# mimic1568_DtoA.net
KiCad netlist of a schematic drawn in EAGLE
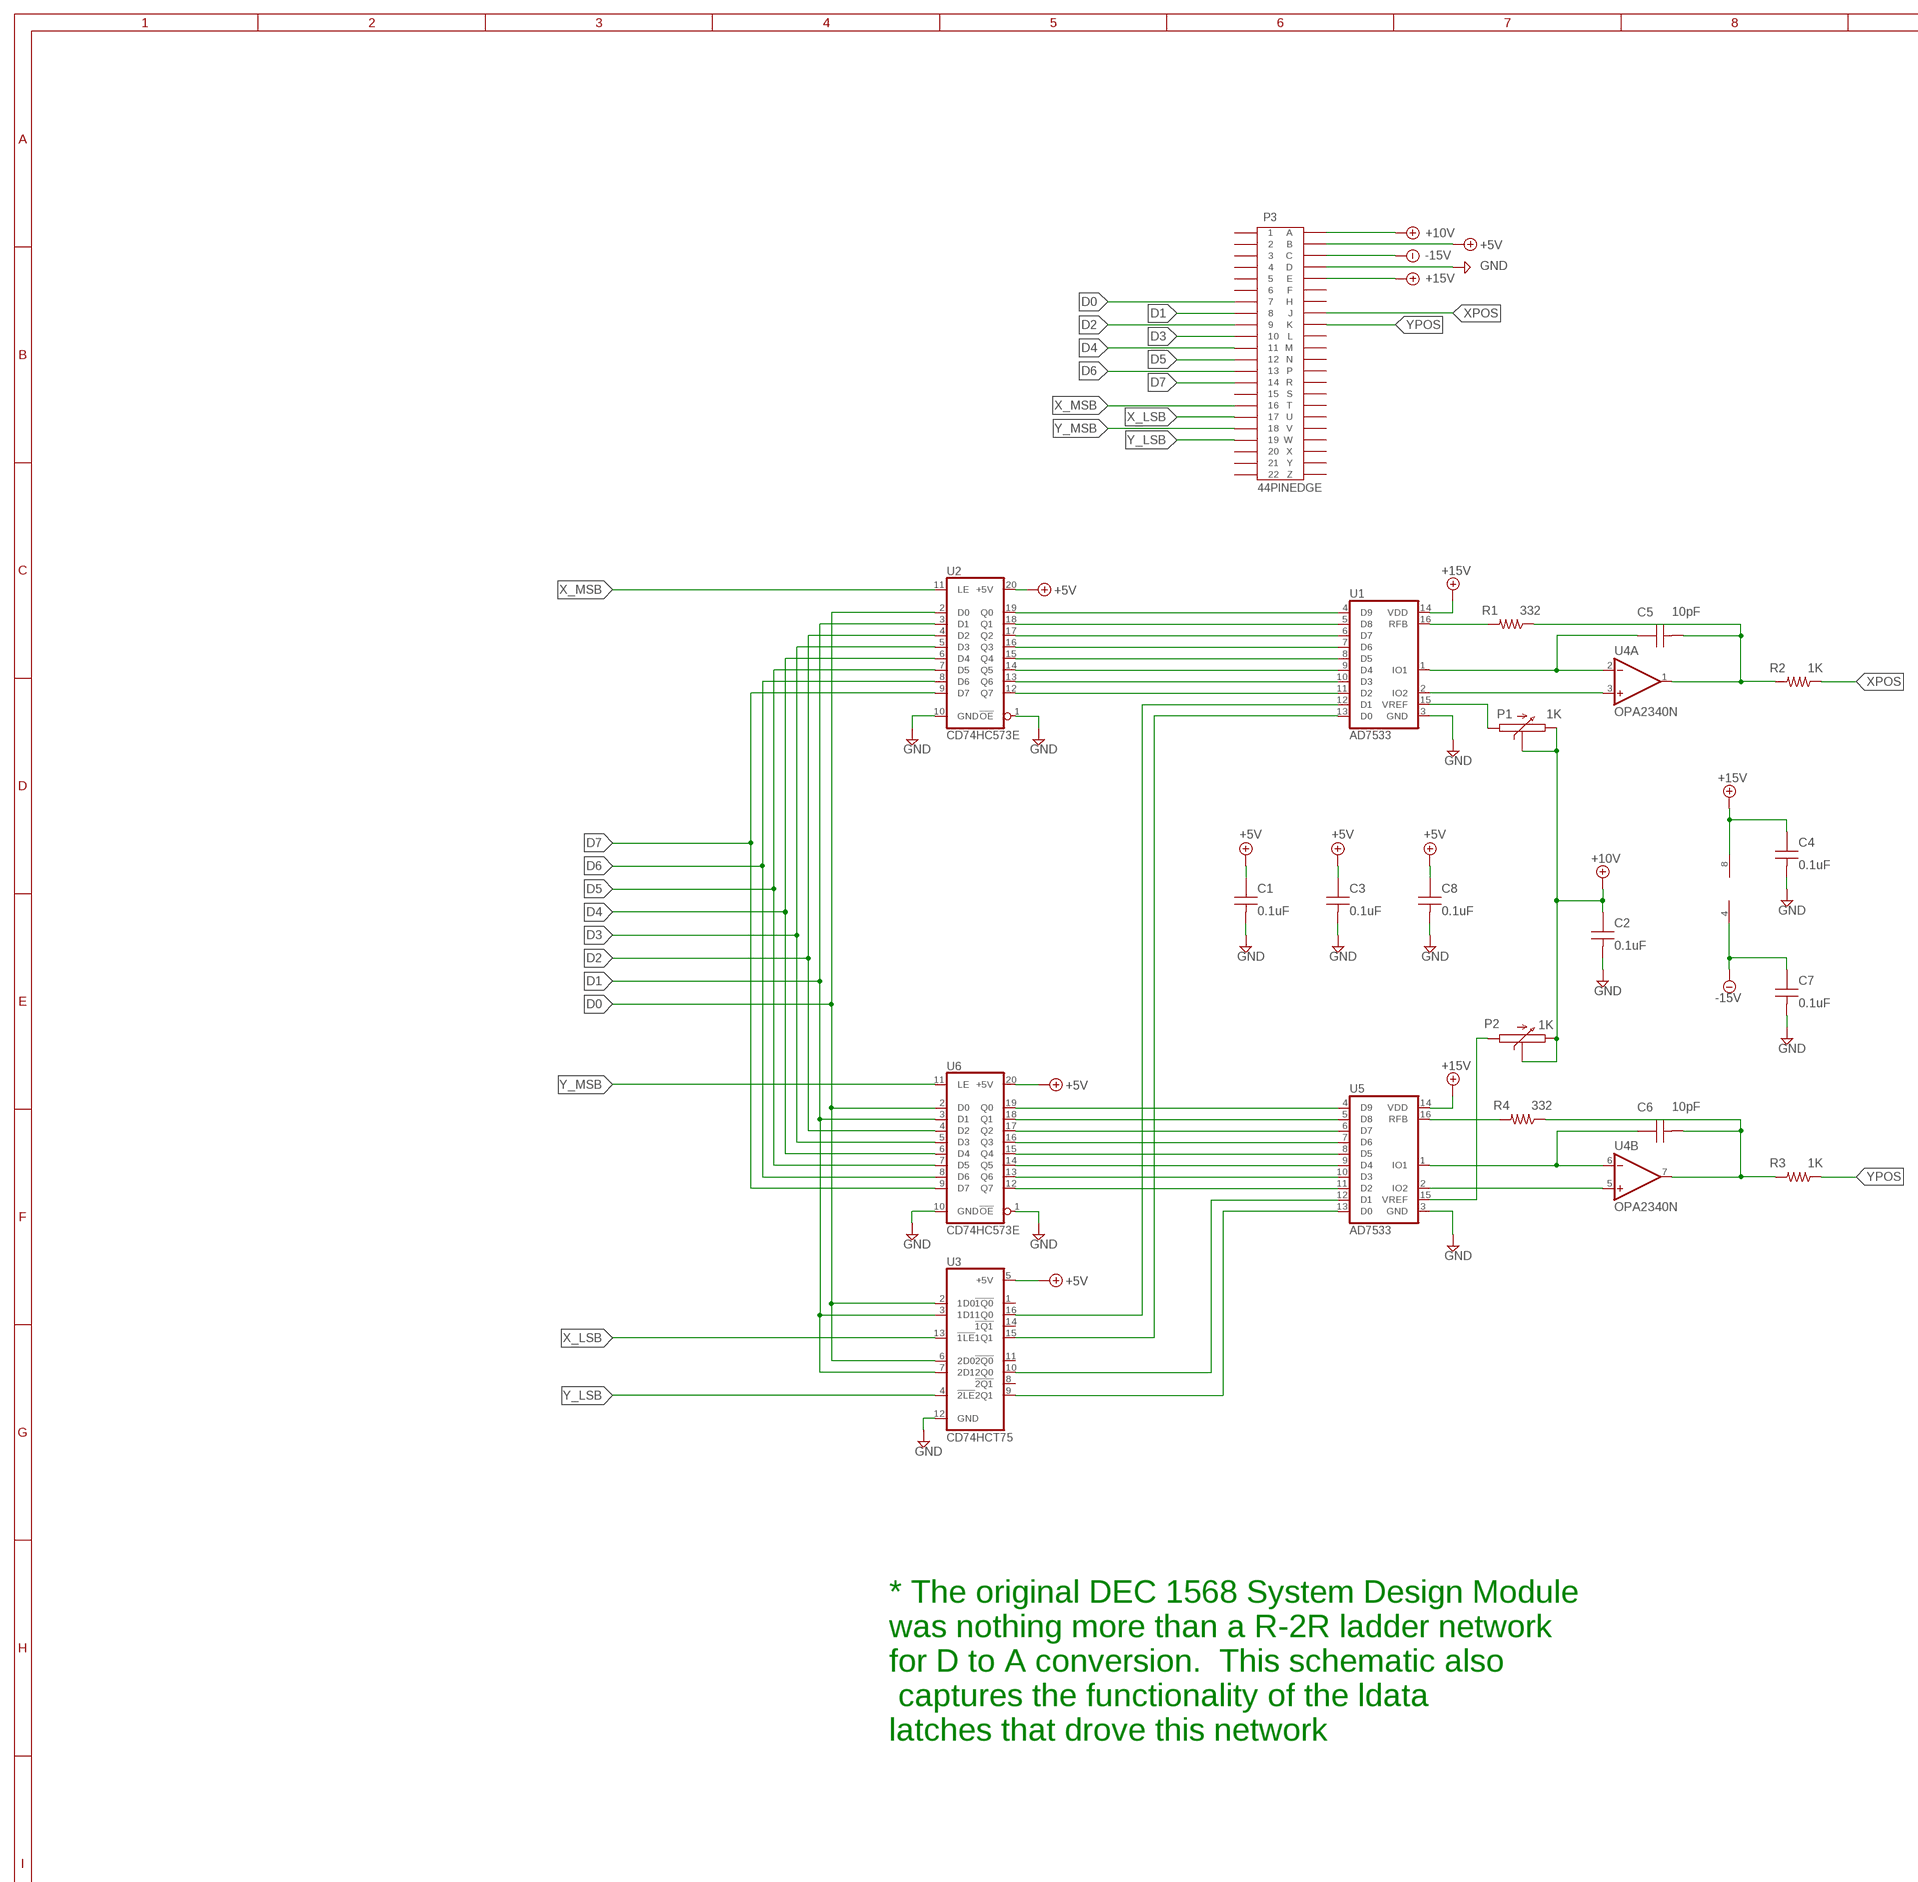
[diagram p0: schematic, sheet 1, part 1 of 2]
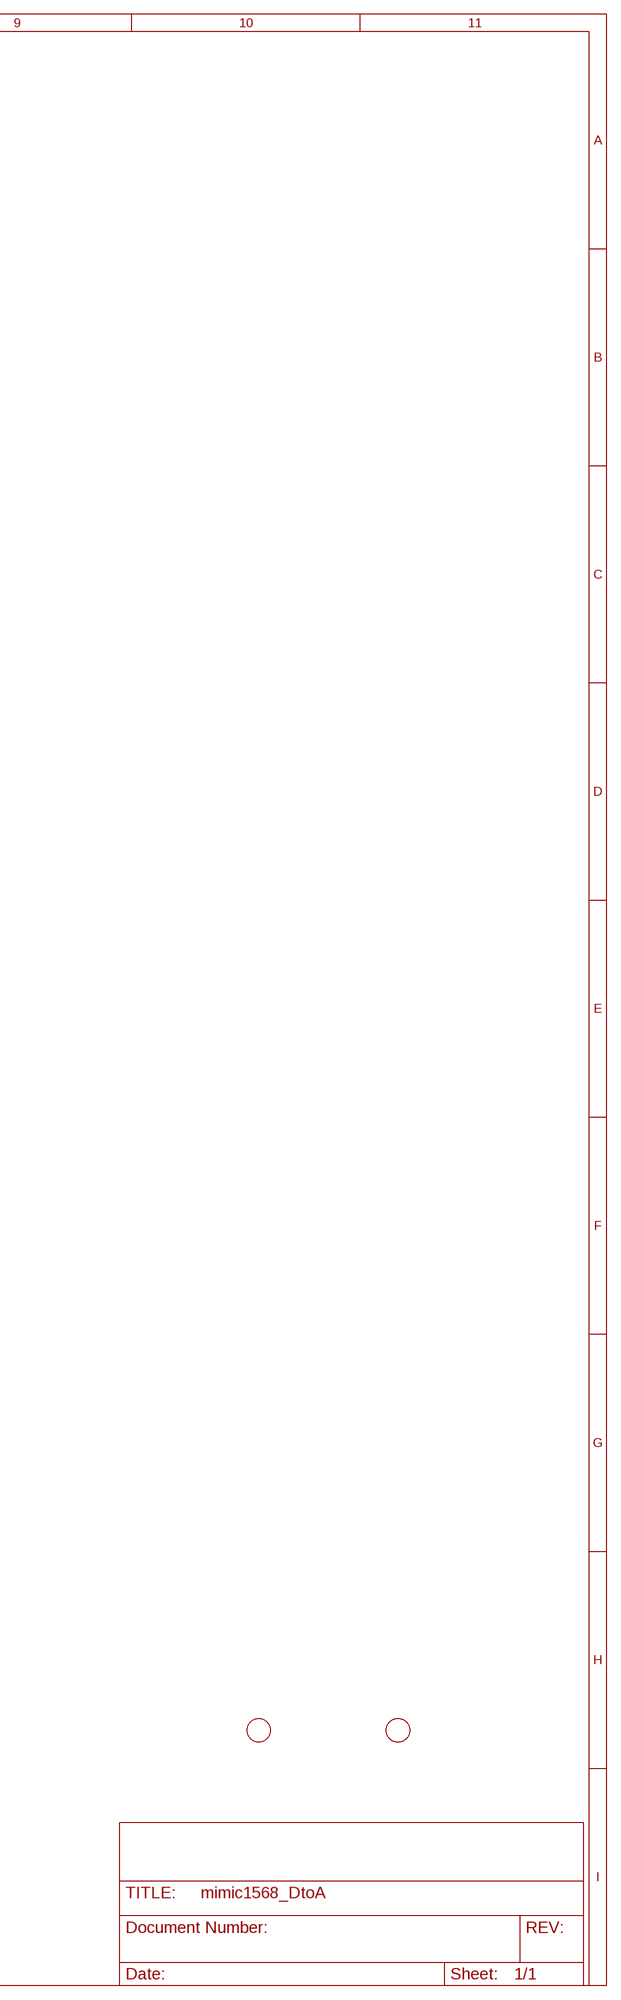
[diagram p1: schematic, sheet 1, part 2 of 2]

(export (version "E")
  (design (tool "Eeschema 10.0.6"))
  (components
    (comp (ref "C1")
      (value "0.1uF")
      (footprint "eagle-import:5MM_TH")
      (fields (field (name "MPN") "FA26X8R2A104KNU06"))
      (libsource (lib "eagle-import") (part "CAP0.1UF100V"))
    )
    (comp (ref "C2")
      (value "0.1uF")
      (footprint "eagle-import:5MM_TH")
      (fields (field (name "MPN") "FA26X8R2A104KNU06"))
      (libsource (lib "eagle-import") (part "CAP0.1UF100V"))
    )
    (comp (ref "C3")
      (value "0.1uF")
      (footprint "eagle-import:5MM_TH")
      (fields (field (name "MPN") "FA26X8R2A104KNU06"))
      (libsource (lib "eagle-import") (part "CAP0.1UF100V"))
    )
    (comp (ref "C4")
      (value "0.1uF")
      (footprint "eagle-import:5MM_TH")
      (fields (field (name "MPN") "FA26X8R2A104KNU06"))
      (libsource (lib "eagle-import") (part "CAP0.1UF100V"))
    )
    (comp (ref "C5")
      (value "10pF")
      (footprint "eagle-import:5MM_TH")
      (fields (field (name "MPN") "FA26X8R2A104KNU06"))
      (libsource (lib "eagle-import") (part "CAP0.1UF100V"))
    )
    (comp (ref "C6")
      (value "10pF")
      (footprint "eagle-import:5MM_TH")
      (fields (field (name "MPN") "FA26X8R2A104KNU06"))
      (libsource (lib "eagle-import") (part "CAP0.1UF100V"))
    )
    (comp (ref "C7")
      (value "0.1uF")
      (footprint "eagle-import:5MM_TH")
      (fields (field (name "MPN") "FA26X8R2A104KNU06"))
      (libsource (lib "eagle-import") (part "CAP0.1UF100V"))
    )
    (comp (ref "C8")
      (value "0.1uF")
      (footprint "eagle-import:5MM_TH")
      (fields (field (name "MPN") "FA26X8R2A104KNU06"))
      (libsource (lib "eagle-import") (part "CAP0.1UF100V"))
    )
    (comp (ref "P1")
      (value "1K")
      (footprint "eagle-import:3006P")
      (libsource (lib "eagle-import") (part "POT-3006P"))
    )
    (comp (ref "P2")
      (value "1K")
      (footprint "eagle-import:3006P")
      (libsource (lib "eagle-import") (part "POT-3006P"))
    )
    (comp (ref "P3")
      (value "44PINEDGE")
      (footprint "eagle-import:44PINEDGE")
      (libsource (lib "eagle-import") (part "44PINEDGE"))
    )
    (comp (ref "R1")
      (value "332")
      (footprint "eagle-import:0207_10")
      (libsource (lib "eagle-import") (part "R-1/4WATT"))
    )
    (comp (ref "R2")
      (value "1K")
      (footprint "eagle-import:0207_10")
      (libsource (lib "eagle-import") (part "R-1/4WATT"))
    )
    (comp (ref "R3")
      (value "1K")
      (footprint "eagle-import:0207_10")
      (libsource (lib "eagle-import") (part "R-1/4WATT"))
    )
    (comp (ref "R4")
      (value "332")
      (footprint "eagle-import:0207_10")
      (libsource (lib "eagle-import") (part "R-1/4WATT"))
    )
    (comp (ref "U$1")
      (value "FIDUCIAL")
      (footprint "eagle-import:FIDUCIAL_1MM")
      (libsource (lib "eagle-import") (part "FIDUCIAL"))
    )
    (comp (ref "U$2")
      (value "FIDUCIAL")
      (footprint "eagle-import:FIDUCIAL_1MM")
      (libsource (lib "eagle-import") (part "FIDUCIAL"))
    )
    (comp (ref "U1")
      (value "AD7533")
      (footprint "eagle-import:DIP-16")
      (libsource (lib "eagle-import") (part "AD7533"))
    )
    (comp (ref "U2")
      (value "CD74HC573E")
      (footprint "eagle-import:DIP-20")
      (libsource (lib "eagle-import") (part "CD74HC573E"))
    )
    (comp (ref "U3")
      (value "CD74HCT75")
      (footprint "eagle-import:DIP-16")
      (libsource (lib "eagle-import") (part "CD74HCT75"))
    )
    (comp (ref "U4")
      (value "OPA2340N")
      (footprint "eagle-import:DIP-08")
      (libsource (lib "eagle-import") (part "OPA2340N"))
    )
    (comp (ref "U5")
      (value "AD7533")
      (footprint "eagle-import:DIP-16")
      (libsource (lib "eagle-import") (part "AD7533"))
    )
    (comp (ref "U6")
      (value "CD74HC573E")
      (footprint "eagle-import:DIP-20")
      (libsource (lib "eagle-import") (part "CD74HC573E"))
    )
  )
  (nets
    (net (code "1") (name "+5V") (class "Default")
      (node (ref "C1") (pin "1") (pinfunction "1_1") (pintype "passive"))
      (node (ref "C3") (pin "1") (pinfunction "1_1") (pintype "passive"))
      (node (ref "C8") (pin "1") (pinfunction "1_1") (pintype "passive"))
      (node (ref "P3") (pin "B") (pinfunction "B_B") (pintype "passive"))
      (node (ref "U2") (pin "20") (pinfunction "+5V_20") (pintype "power_in"))
      (node (ref "U3") (pin "5") (pinfunction "+5V_5") (pintype "power_in"))
      (node (ref "U6") (pin "20") (pinfunction "+5V_20") (pintype "power_in"))
    )
    (net (code "2") (name "+10V") (class "Default")
      (node (ref "C2") (pin "1") (pinfunction "1_1") (pintype "passive"))
      (node (ref "P1") (pin "2") (pinfunction "2_2") (pintype "passive"))
      (node (ref "P1") (pin "3") (pinfunction "3_3") (pintype "passive"))
      (node (ref "P2") (pin "2") (pinfunction "2_2") (pintype "passive"))
      (node (ref "P2") (pin "3") (pinfunction "3_3") (pintype "passive"))
      (node (ref "P3") (pin "A") (pinfunction "A_A") (pintype "passive"))
    )
    (net (code "3") (name "+15V") (class "Default")
      (node (ref "C4") (pin "1") (pinfunction "1_1") (pintype "passive"))
      (node (ref "P3") (pin "E") (pinfunction "E_E") (pintype "passive"))
      (node (ref "U1") (pin "14") (pinfunction "VDD_14") (pintype "power_in"))
      (node (ref "U4") (pin "8") (pinfunction "V+_8") (pintype "power_in"))
      (node (ref "U5") (pin "14") (pinfunction "VDD_14") (pintype "power_in"))
    )
    (net (code "4") (name "-15V") (class "Default")
      (node (ref "C7") (pin "1") (pinfunction "1_1") (pintype "passive"))
      (node (ref "P3") (pin "C") (pinfunction "C_C") (pintype "passive"))
      (node (ref "U4") (pin "4") (pinfunction "V-_4") (pintype "power_in"))
    )
    (net (code "5") (name "D0") (class "Default")
      (node (ref "P3") (pin "7") (pinfunction "7_7") (pintype "passive"))
      (node (ref "U2") (pin "2") (pinfunction "D0_2") (pintype "input"))
      (node (ref "U3") (pin "2") (pinfunction "1D0_2") (pintype "input"))
      (node (ref "U3") (pin "6") (pinfunction "2D0_6") (pintype "input"))
      (node (ref "U6") (pin "2") (pinfunction "D0_2") (pintype "input"))
    )
    (net (code "6") (name "D1") (class "Default")
      (node (ref "P3") (pin "8") (pinfunction "8_8") (pintype "passive"))
      (node (ref "U2") (pin "3") (pinfunction "D1_3") (pintype "input"))
      (node (ref "U3") (pin "3") (pinfunction "1D1_3") (pintype "input"))
      (node (ref "U3") (pin "7") (pinfunction "2D1_7") (pintype "input"))
      (node (ref "U6") (pin "3") (pinfunction "D1_3") (pintype "input"))
    )
    (net (code "7") (name "D2") (class "Default")
      (node (ref "P3") (pin "9") (pinfunction "9_9") (pintype "passive"))
      (node (ref "U2") (pin "4") (pinfunction "D2_4") (pintype "input"))
      (node (ref "U6") (pin "4") (pinfunction "D2_4") (pintype "input"))
    )
    (net (code "8") (name "D3") (class "Default")
      (node (ref "P3") (pin "10") (pinfunction "10_10") (pintype "passive"))
      (node (ref "U2") (pin "5") (pinfunction "D3_5") (pintype "input"))
      (node (ref "U6") (pin "5") (pinfunction "D3_5") (pintype "input"))
    )
    (net (code "9") (name "D4") (class "Default")
      (node (ref "P3") (pin "11") (pinfunction "11_11") (pintype "passive"))
      (node (ref "U2") (pin "6") (pinfunction "D4_6") (pintype "input"))
      (node (ref "U6") (pin "6") (pinfunction "D4_6") (pintype "input"))
    )
    (net (code "10") (name "D5") (class "Default")
      (node (ref "P3") (pin "12") (pinfunction "12_12") (pintype "passive"))
      (node (ref "U2") (pin "7") (pinfunction "D5_7") (pintype "input"))
      (node (ref "U6") (pin "7") (pinfunction "D5_7") (pintype "input"))
    )
    (net (code "11") (name "D6") (class "Default")
      (node (ref "P3") (pin "13") (pinfunction "13_13") (pintype "passive"))
      (node (ref "U2") (pin "8") (pinfunction "D6_8") (pintype "input"))
      (node (ref "U6") (pin "8") (pinfunction "D6_8") (pintype "input"))
    )
    (net (code "12") (name "D7") (class "Default")
      (node (ref "P3") (pin "14") (pinfunction "14_14") (pintype "passive"))
      (node (ref "U2") (pin "9") (pinfunction "D7_9") (pintype "input"))
      (node (ref "U6") (pin "9") (pinfunction "D7_9") (pintype "input"))
    )
    (net (code "13") (name "GND") (class "Default")
      (node (ref "C1") (pin "2") (pinfunction "2_2") (pintype "passive"))
      (node (ref "C2") (pin "2") (pinfunction "2_2") (pintype "passive"))
      (node (ref "C3") (pin "2") (pinfunction "2_2") (pintype "passive"))
      (node (ref "C4") (pin "2") (pinfunction "2_2") (pintype "passive"))
      (node (ref "C7") (pin "2") (pinfunction "2_2") (pintype "passive"))
      (node (ref "C8") (pin "2") (pinfunction "2_2") (pintype "passive"))
      (node (ref "P3") (pin "D") (pinfunction "D_D") (pintype "passive"))
      (node (ref "U1") (pin "3") (pinfunction "GND_3") (pintype "power_in"))
      (node (ref "U2") (pin "1") (pinfunction "~{OE}_1") (pintype "input"))
      (node (ref "U2") (pin "10") (pinfunction "GND_10") (pintype "power_in"))
      (node (ref "U3") (pin "12") (pinfunction "GND_12") (pintype "power_in"))
      (node (ref "U5") (pin "3") (pinfunction "GND_3") (pintype "power_in"))
      (node (ref "U6") (pin "1") (pinfunction "~{OE}_1") (pintype "input"))
      (node (ref "U6") (pin "10") (pinfunction "GND_10") (pintype "power_in"))
    )
    (net (code "14") (name "Net-(R1-P$1)") (class "Default")
      (node (ref "C5") (pin "2") (pinfunction "2_2") (pintype "passive"))
      (node (ref "R1") (pin "1") (pinfunction "P$1_1") (pintype "passive"))
      (node (ref "R2") (pin "2") (pinfunction "P$2_2") (pintype "passive"))
      (node (ref "U4") (pin "1") (pinfunction "OUT_1") (pintype "output"))
    )
    (net (code "15") (name "Net-(R1-P$2)") (class "Default")
      (node (ref "R1") (pin "2") (pinfunction "P$2_2") (pintype "passive"))
      (node (ref "U1") (pin "16") (pinfunction "RFB_16") (pintype "input"))
    )
    (net (code "16") (name "Net-(R3-P$2)") (class "Default")
      (node (ref "C6") (pin "2") (pinfunction "2_2") (pintype "passive"))
      (node (ref "R3") (pin "2") (pinfunction "P$2_2") (pintype "passive"))
      (node (ref "R4") (pin "1") (pinfunction "P$1_1") (pintype "passive"))
      (node (ref "U4") (pin "7") (pinfunction "OUT_7") (pintype "output"))
    )
    (net (code "17") (name "Net-(R4-P$2)") (class "Default")
      (node (ref "R4") (pin "2") (pinfunction "P$2_2") (pintype "passive"))
      (node (ref "U5") (pin "16") (pinfunction "RFB_16") (pintype "input"))
    )
    (net (code "18") (name "Net-(U1-D0)") (class "Default")
      (node (ref "U1") (pin "13") (pinfunction "D0_13") (pintype "input"))
      (node (ref "U3") (pin "15") (pinfunction "1Q1_15") (pintype "output"))
    )
    (net (code "19") (name "Net-(U1-D1)") (class "Default")
      (node (ref "U1") (pin "12") (pinfunction "D1_12") (pintype "input"))
      (node (ref "U3") (pin "16") (pinfunction "1Q0_16") (pintype "output"))
    )
    (net (code "20") (name "Net-(U1-D2)") (class "Default")
      (node (ref "U1") (pin "11") (pinfunction "D2_11") (pintype "input"))
      (node (ref "U2") (pin "12") (pinfunction "Q7_12") (pintype "tri_state"))
    )
    (net (code "21") (name "Net-(U1-D3)") (class "Default")
      (node (ref "U1") (pin "10") (pinfunction "D3_10") (pintype "input"))
      (node (ref "U2") (pin "13") (pinfunction "Q6_13") (pintype "tri_state"))
    )
    (net (code "22") (name "Net-(U1-D4)") (class "Default")
      (node (ref "U1") (pin "9") (pinfunction "D4_9") (pintype "input"))
      (node (ref "U2") (pin "14") (pinfunction "Q5_14") (pintype "tri_state"))
    )
    (net (code "23") (name "Net-(U1-D5)") (class "Default")
      (node (ref "U1") (pin "8") (pinfunction "D5_8") (pintype "input"))
      (node (ref "U2") (pin "15") (pinfunction "Q4_15") (pintype "tri_state"))
    )
    (net (code "24") (name "Net-(U1-D6)") (class "Default")
      (node (ref "U1") (pin "7") (pinfunction "D6_7") (pintype "input"))
      (node (ref "U2") (pin "16") (pinfunction "Q3_16") (pintype "tri_state"))
    )
    (net (code "25") (name "Net-(U1-D7)") (class "Default")
      (node (ref "U1") (pin "6") (pinfunction "D7_6") (pintype "input"))
      (node (ref "U2") (pin "17") (pinfunction "Q2_17") (pintype "tri_state"))
    )
    (net (code "26") (name "Net-(U1-D8)") (class "Default")
      (node (ref "U1") (pin "5") (pinfunction "D8_5") (pintype "input"))
      (node (ref "U2") (pin "18") (pinfunction "Q1_18") (pintype "tri_state"))
    )
    (net (code "27") (name "Net-(U1-D9)") (class "Default")
      (node (ref "U1") (pin "4") (pinfunction "D9_4") (pintype "input"))
      (node (ref "U2") (pin "19") (pinfunction "Q0_19") (pintype "tri_state"))
    )
    (net (code "28") (name "Net-(U1-IO1)") (class "Default")
      (node (ref "C5") (pin "1") (pinfunction "1_1") (pintype "passive"))
      (node (ref "U1") (pin "1") (pinfunction "IO1_1") (pintype "output"))
      (node (ref "U4") (pin "2") (pinfunction "-IN_2") (pintype "input"))
    )
    (net (code "29") (name "Net-(U1-IO2)") (class "Default")
      (node (ref "U1") (pin "2") (pinfunction "IO2_2") (pintype "output"))
      (node (ref "U4") (pin "3") (pinfunction "+IN_3") (pintype "input"))
    )
    (net (code "30") (name "Net-(U1-VREF)") (class "Default")
      (node (ref "P1") (pin "1") (pinfunction "1_1") (pintype "passive"))
      (node (ref "U1") (pin "15") (pinfunction "VREF_15") (pintype "power_in"))
    )
    (net (code "31") (name "Net-(U3-2Q0)") (class "Default")
      (node (ref "U3") (pin "10") (pinfunction "2Q0_10") (pintype "output"))
      (node (ref "U5") (pin "12") (pinfunction "D1_12") (pintype "input"))
    )
    (net (code "32") (name "Net-(U3-2Q1)") (class "Default")
      (node (ref "U3") (pin "9") (pinfunction "2Q1_9") (pintype "output"))
      (node (ref "U5") (pin "13") (pinfunction "D0_13") (pintype "input"))
    )
    (net (code "33") (name "Net-(U4B-+IN)") (class "Default")
      (node (ref "U4") (pin "5") (pinfunction "+IN_5") (pintype "input"))
      (node (ref "U5") (pin "2") (pinfunction "IO2_2") (pintype "output"))
    )
    (net (code "34") (name "Net-(U4B--IN)") (class "Default")
      (node (ref "C6") (pin "1") (pinfunction "1_1") (pintype "passive"))
      (node (ref "U4") (pin "6") (pinfunction "-IN_6") (pintype "input"))
      (node (ref "U5") (pin "1") (pinfunction "IO1_1") (pintype "output"))
    )
    (net (code "35") (name "Net-(U5-D2)") (class "Default")
      (node (ref "U5") (pin "11") (pinfunction "D2_11") (pintype "input"))
      (node (ref "U6") (pin "12") (pinfunction "Q7_12") (pintype "tri_state"))
    )
    (net (code "36") (name "Net-(U5-D3)") (class "Default")
      (node (ref "U5") (pin "10") (pinfunction "D3_10") (pintype "input"))
      (node (ref "U6") (pin "13") (pinfunction "Q6_13") (pintype "tri_state"))
    )
    (net (code "37") (name "Net-(U5-D4)") (class "Default")
      (node (ref "U5") (pin "9") (pinfunction "D4_9") (pintype "input"))
      (node (ref "U6") (pin "14") (pinfunction "Q5_14") (pintype "tri_state"))
    )
    (net (code "38") (name "Net-(U5-D5)") (class "Default")
      (node (ref "U5") (pin "8") (pinfunction "D5_8") (pintype "input"))
      (node (ref "U6") (pin "15") (pinfunction "Q4_15") (pintype "tri_state"))
    )
    (net (code "39") (name "Net-(U5-D6)") (class "Default")
      (node (ref "U5") (pin "7") (pinfunction "D6_7") (pintype "input"))
      (node (ref "U6") (pin "16") (pinfunction "Q3_16") (pintype "tri_state"))
    )
    (net (code "40") (name "Net-(U5-D7)") (class "Default")
      (node (ref "U5") (pin "6") (pinfunction "D7_6") (pintype "input"))
      (node (ref "U6") (pin "17") (pinfunction "Q2_17") (pintype "tri_state"))
    )
    (net (code "41") (name "Net-(U5-D8)") (class "Default")
      (node (ref "U5") (pin "5") (pinfunction "D8_5") (pintype "input"))
      (node (ref "U6") (pin "18") (pinfunction "Q1_18") (pintype "tri_state"))
    )
    (net (code "42") (name "Net-(U5-D9)") (class "Default")
      (node (ref "U5") (pin "4") (pinfunction "D9_4") (pintype "input"))
      (node (ref "U6") (pin "19") (pinfunction "Q0_19") (pintype "tri_state"))
    )
    (net (code "43") (name "Net-(U5-VREF)") (class "Default")
      (node (ref "P2") (pin "1") (pinfunction "1_1") (pintype "passive"))
      (node (ref "U5") (pin "15") (pinfunction "VREF_15") (pintype "power_in"))
    )
    (net (code "44") (name "XPOS") (class "Default")
      (node (ref "P3") (pin "J") (pinfunction "J_J") (pintype "passive"))
      (node (ref "R2") (pin "1") (pinfunction "P$1_1") (pintype "passive"))
    )
    (net (code "45") (name "X_LSB") (class "Default")
      (node (ref "P3") (pin "17") (pinfunction "17_17") (pintype "passive"))
      (node (ref "U3") (pin "13") (pinfunction "~{1LE}_13") (pintype "input"))
    )
    (net (code "46") (name "X_MSB") (class "Default")
      (node (ref "P3") (pin "16") (pinfunction "16_16") (pintype "passive"))
      (node (ref "U2") (pin "11") (pinfunction "LE_11") (pintype "input"))
    )
    (net (code "47") (name "YPOS") (class "Default")
      (node (ref "P3") (pin "K") (pinfunction "K_K") (pintype "passive"))
      (node (ref "R3") (pin "1") (pinfunction "P$1_1") (pintype "passive"))
    )
    (net (code "48") (name "Y_LSB") (class "Default")
      (node (ref "P3") (pin "19") (pinfunction "19_19") (pintype "passive"))
      (node (ref "U3") (pin "4") (pinfunction "~{2LE}_4") (pintype "input"))
    )
    (net (code "49") (name "Y_MSB") (class "Default")
      (node (ref "P3") (pin "18") (pinfunction "18_18") (pintype "passive"))
      (node (ref "U6") (pin "11") (pinfunction "LE_11") (pintype "input"))
    )
    (net (code "50") (name "unconnected-(P3-Pad1)") (class "Default")
      (node (ref "P3") (pin "1") (pinfunction "1_1") (pintype "passive"))
    )
    (net (code "51") (name "unconnected-(P3-Pad2)") (class "Default")
      (node (ref "P3") (pin "2") (pinfunction "2_2") (pintype "passive"))
    )
    (net (code "52") (name "unconnected-(P3-Pad3)") (class "Default")
      (node (ref "P3") (pin "3") (pinfunction "3_3") (pintype "passive"))
    )
    (net (code "53") (name "unconnected-(P3-Pad4)") (class "Default")
      (node (ref "P3") (pin "4") (pinfunction "4_4") (pintype "passive"))
    )
    (net (code "54") (name "unconnected-(P3-Pad5)") (class "Default")
      (node (ref "P3") (pin "5") (pinfunction "5_5") (pintype "passive"))
    )
    (net (code "55") (name "unconnected-(P3-Pad6)") (class "Default")
      (node (ref "P3") (pin "6") (pinfunction "6_6") (pintype "passive"))
    )
    (net (code "56") (name "unconnected-(P3-Pad15)") (class "Default")
      (node (ref "P3") (pin "15") (pinfunction "15_15") (pintype "passive"))
    )
    (net (code "57") (name "unconnected-(P3-Pad20)") (class "Default")
      (node (ref "P3") (pin "20") (pinfunction "20_20") (pintype "passive"))
    )
    (net (code "58") (name "unconnected-(P3-Pad21)") (class "Default")
      (node (ref "P3") (pin "21") (pinfunction "21_21") (pintype "passive"))
    )
    (net (code "59") (name "unconnected-(P3-Pad22)") (class "Default")
      (node (ref "P3") (pin "22") (pinfunction "22_22") (pintype "passive"))
    )
    (net (code "60") (name "unconnected-(P3-PadF)") (class "Default")
      (node (ref "P3") (pin "F") (pinfunction "F_F") (pintype "passive"))
    )
    (net (code "61") (name "unconnected-(P3-PadH)") (class "Default")
      (node (ref "P3") (pin "H") (pinfunction "H_H") (pintype "passive"))
    )
    (net (code "62") (name "unconnected-(P3-PadL)") (class "Default")
      (node (ref "P3") (pin "L") (pinfunction "L_L") (pintype "passive"))
    )
    (net (code "63") (name "unconnected-(P3-PadM)") (class "Default")
      (node (ref "P3") (pin "M") (pinfunction "M_M") (pintype "passive"))
    )
    (net (code "64") (name "unconnected-(P3-PadN)") (class "Default")
      (node (ref "P3") (pin "N") (pinfunction "N_N") (pintype "passive"))
    )
    (net (code "65") (name "unconnected-(P3-PadP)") (class "Default")
      (node (ref "P3") (pin "P") (pinfunction "P_P") (pintype "passive"))
    )
    (net (code "66") (name "unconnected-(P3-PadR)") (class "Default")
      (node (ref "P3") (pin "R") (pinfunction "R_R") (pintype "passive"))
    )
    (net (code "67") (name "unconnected-(P3-PadS)") (class "Default")
      (node (ref "P3") (pin "S") (pinfunction "S_S") (pintype "passive"))
    )
    (net (code "68") (name "unconnected-(P3-PadT)") (class "Default")
      (node (ref "P3") (pin "T") (pinfunction "T_T") (pintype "passive"))
    )
    (net (code "69") (name "unconnected-(P3-PadU)") (class "Default")
      (node (ref "P3") (pin "U") (pinfunction "U_U") (pintype "passive"))
    )
    (net (code "70") (name "unconnected-(P3-PadV)") (class "Default")
      (node (ref "P3") (pin "V") (pinfunction "V_V") (pintype "passive"))
    )
    (net (code "71") (name "unconnected-(P3-PadW)") (class "Default")
      (node (ref "P3") (pin "W") (pinfunction "W_W") (pintype "passive"))
    )
    (net (code "72") (name "unconnected-(P3-PadX)") (class "Default")
      (node (ref "P3") (pin "X") (pinfunction "X_X") (pintype "passive"))
    )
    (net (code "73") (name "unconnected-(P3-PadY)") (class "Default")
      (node (ref "P3") (pin "Y") (pinfunction "Y_Y") (pintype "passive"))
    )
    (net (code "74") (name "unconnected-(P3-PadZ)") (class "Default")
      (node (ref "P3") (pin "Z") (pinfunction "Z_Z") (pintype "passive"))
    )
    (net (code "75") (name "unconnected-(U3-~{1Q0}-Pad1)") (class "Default")
      (node (ref "U3") (pin "1") (pinfunction "~{1Q0}_1") (pintype "output"))
    )
    (net (code "76") (name "unconnected-(U3-~{1Q1}-Pad14)") (class "Default")
      (node (ref "U3") (pin "14") (pinfunction "~{1Q1}_14") (pintype "output"))
    )
    (net (code "77") (name "unconnected-(U3-~{2Q0}-Pad11)") (class "Default")
      (node (ref "U3") (pin "11") (pinfunction "~{2Q0}_11") (pintype "output"))
    )
    (net (code "78") (name "unconnected-(U3-~{2Q1}-Pad8)") (class "Default")
      (node (ref "U3") (pin "8") (pinfunction "~{2Q1}_8") (pintype "output"))
    )
  )
)
